# sang_bu.net
KiCad netlist of a schematic drawn in EAGLE
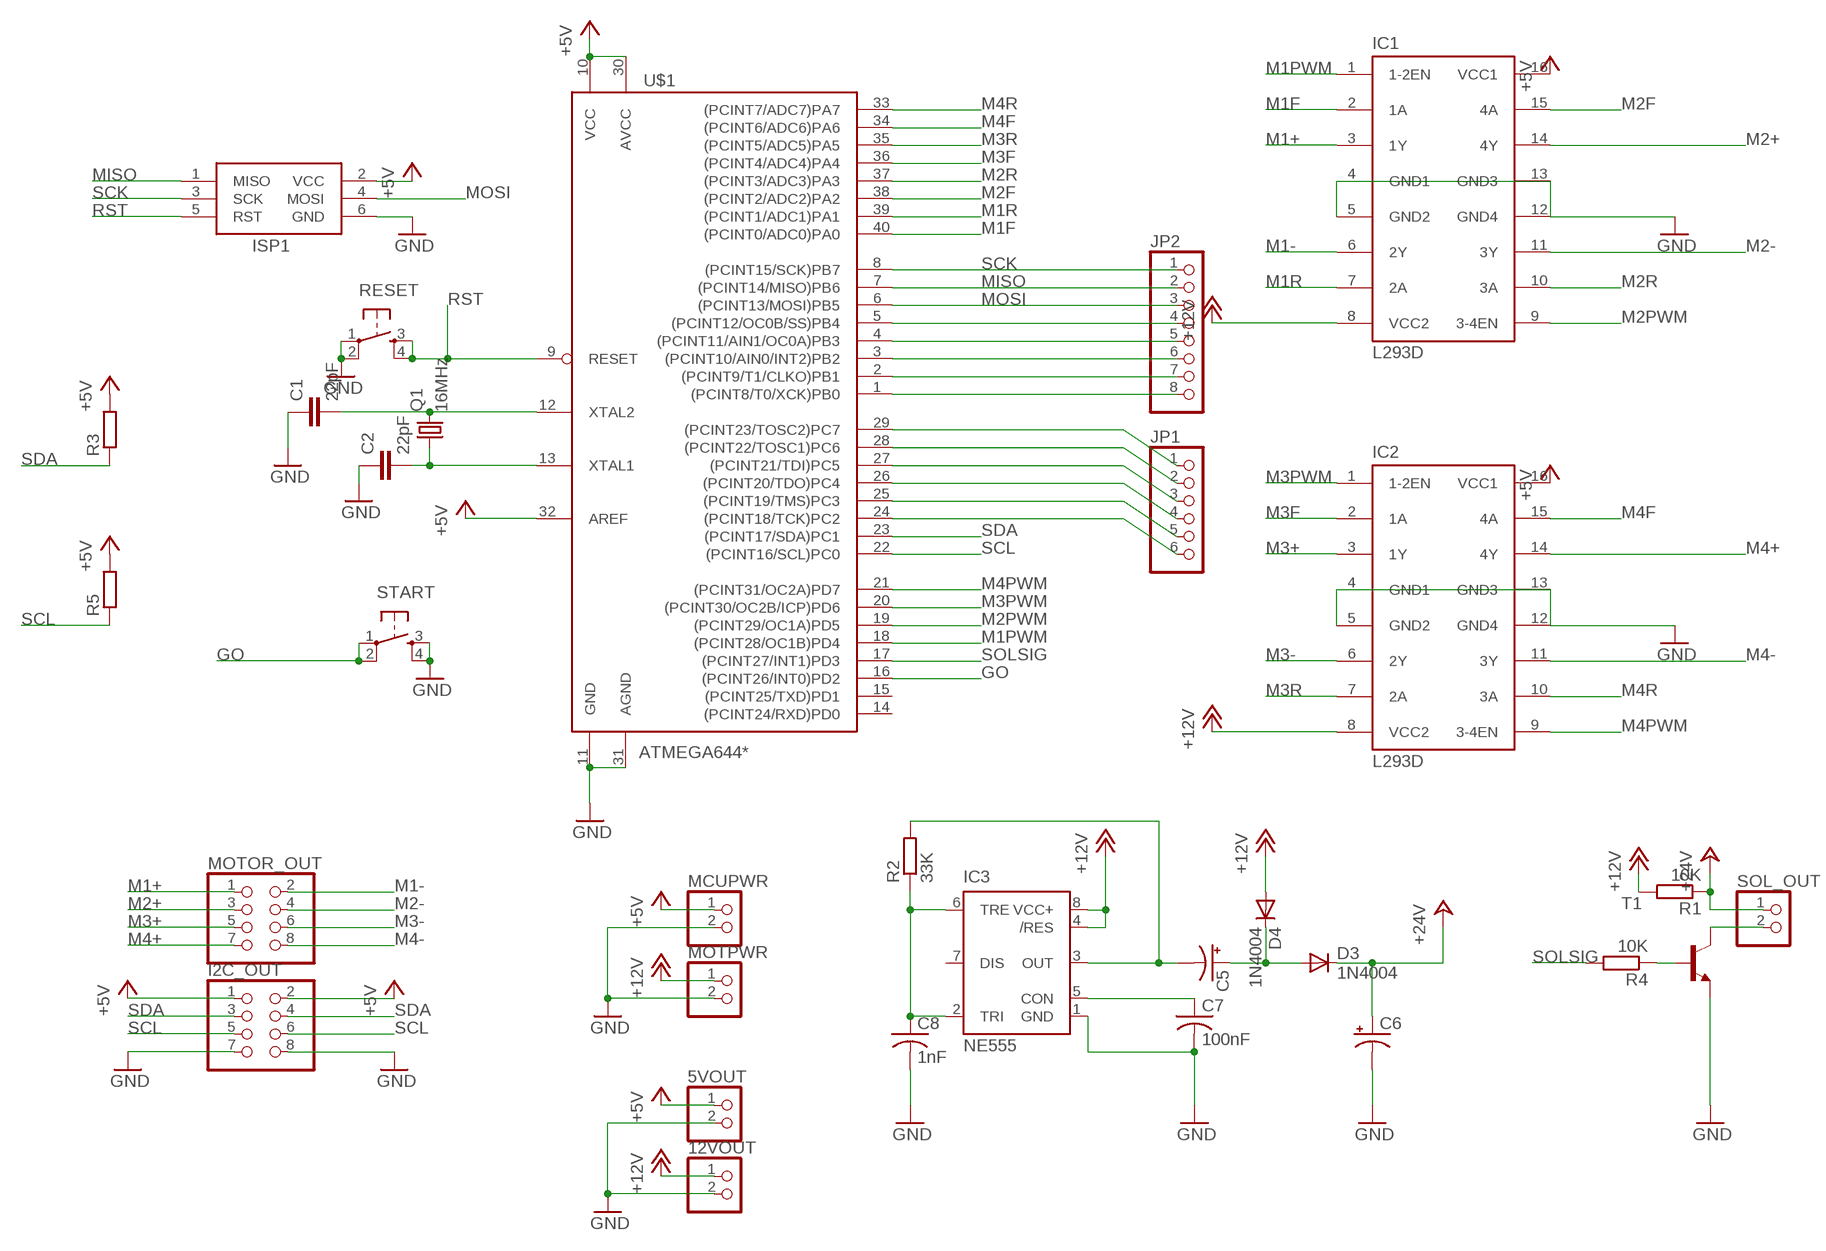
[diagram p0: schematic, sheet 1]

(export (version "E")
  (design (tool "Eeschema 10.0.6"))
  (components
    (comp (ref "5VOUT")
      (value "PINHD-1X2")
      (footprint "eagle-import:1X02")
      (libsource (lib "eagle-import") (part "PINHD-1X2"))
    )
    (comp (ref "12VOUT")
      (value "PINHD-1X2")
      (footprint "eagle-import:1X02")
      (libsource (lib "eagle-import") (part "PINHD-1X2"))
    )
    (comp (ref "C1")
      (value "22pF")
      (footprint "eagle-import:C2.5-2")
      (libsource (lib "eagle-import") (part "C2.5/2"))
    )
    (comp (ref "C2")
      (value "22pF")
      (footprint "eagle-import:C2.5-2")
      (libsource (lib "eagle-import") (part "C2.5/2"))
    )
    (comp (ref "C5")
      (value "CPOL-USE7.5-18")
      (footprint "eagle-import:E7,5-18")
      (libsource (lib "eagle-import") (part "CPOL-USE7.5-18"))
    )
    (comp (ref "C6")
      (value "CPOL-USE7.5-18")
      (footprint "eagle-import:E7,5-18")
      (libsource (lib "eagle-import") (part "CPOL-USE7.5-18"))
    )
    (comp (ref "C7")
      (value "100nF")
      (footprint "eagle-import:C025-030X050")
      (libsource (lib "eagle-import") (part "C-US025-030X050"))
    )
    (comp (ref "C8")
      (value "1nF")
      (footprint "eagle-import:C025-030X050")
      (libsource (lib "eagle-import") (part "C-US025-030X050"))
    )
    (comp (ref "D3")
      (value "1N4004")
      (footprint "eagle-import:DO41-10")
      (libsource (lib "eagle-import") (part "1N4004"))
    )
    (comp (ref "D4")
      (value "1N4004")
      (footprint "eagle-import:DO41-10")
      (libsource (lib "eagle-import") (part "1N4004"))
    )
    (comp (ref "I2C_OUT")
      (value "PINHD-2X4")
      (footprint "eagle-import:2X04")
      (libsource (lib "eagle-import") (part "PINHD-2X4"))
    )
    (comp (ref "IC1")
      (value "L293D")
      (footprint "eagle-import:DIL16")
      (libsource (lib "eagle-import") (part "L293D"))
    )
    (comp (ref "IC2")
      (value "L293D")
      (footprint "eagle-import:DIL16")
      (libsource (lib "eagle-import") (part "L293D"))
    )
    (comp (ref "IC3")
      (value "NE555")
      (footprint "eagle-import:DIL-08")
      (fields (field (name "MF") "Arrow Electronics") (field (name "MPN") "NE555N"))
      (libsource (lib "eagle-import") (part "NE555"))
    )
    (comp (ref "ISP1")
      (value "AVRISP-6")
      (footprint "eagle-import:AVRISP")
      (libsource (lib "eagle-import") (part "AVRISP-6"))
    )
    (comp (ref "JP1")
      (value "PINHD-1X6")
      (footprint "eagle-import:1X06")
      (libsource (lib "eagle-import") (part "PINHD-1X6"))
    )
    (comp (ref "JP2")
      (value "PINHD-1X8BIG")
      (footprint "eagle-import:1X08-BIG")
      (libsource (lib "eagle-import") (part "PINHD-1X8BIG"))
    )
    (comp (ref "MCUPWR")
      (value "PINHD-1X2")
      (footprint "eagle-import:1X02")
      (libsource (lib "eagle-import") (part "PINHD-1X2"))
    )
    (comp (ref "MOTOR_OUT")
      (value "PINHD-2X4")
      (footprint "eagle-import:2X04")
      (libsource (lib "eagle-import") (part "PINHD-2X4"))
    )
    (comp (ref "MOTPWR")
      (value "PINHD-1X2")
      (footprint "eagle-import:1X02")
      (libsource (lib "eagle-import") (part "PINHD-1X2"))
    )
    (comp (ref "Q1")
      (value "16MHz")
      (footprint "eagle-import:HC49U70")
      (libsource (lib "eagle-import") (part "CRYSTALHC49U70"))
    )
    (comp (ref "R1")
      (value "10K")
      (footprint "eagle-import:0207_10")
      (libsource (lib "eagle-import") (part "resistor_R-EU_0207/10"))
    )
    (comp (ref "R2")
      (value "33K")
      (footprint "eagle-import:0207_10")
      (libsource (lib "eagle-import") (part "R-EU_0207/10"))
    )
    (comp (ref "R3")
      (value "R-EU_0204/7")
      (footprint "eagle-import:0204_7")
      (libsource (lib "eagle-import") (part "resistor_R-EU_0204/7"))
    )
    (comp (ref "R4")
      (value "10K")
      (footprint "eagle-import:0207_10")
      (libsource (lib "eagle-import") (part "resistor_R-EU_0207/10"))
    )
    (comp (ref "R5")
      (value "R-EU_0204/7")
      (footprint "eagle-import:0204_7")
      (libsource (lib "eagle-import") (part "resistor_R-EU_0204/7"))
    )
    (comp (ref "RESET")
      (value "TAC_SWITCHPTH")
      (footprint "eagle-import:TACTILE-PTH")
      (libsource (lib "eagle-import") (part "TAC_SWITCHPTH"))
    )
    (comp (ref "SOL_OUT")
      (value "PINHD-1X2")
      (footprint "eagle-import:1X02")
      (libsource (lib "eagle-import") (part "PINHD-1X2"))
    )
    (comp (ref "START")
      (value "TAC_SWITCHPTH")
      (footprint "eagle-import:TACTILE-PTH")
      (libsource (lib "eagle-import") (part "TAC_SWITCHPTH"))
    )
    (comp (ref "T1")
      (value "2N2218-NPN-TO39-EBC")
      (footprint "eagle-import:TO39")
      (libsource (lib "eagle-import") (part "-NPN-TO39-EBC2N2218"))
    )
    (comp (ref "U$1")
      (value "ATMEGA644*")
      (footprint "eagle-import:ATMEGA644")
      (libsource (lib "eagle-import") (part "ATMEGA644"))
    )
  )
  (nets
    (net (code "1") (name "+5V") (class "Default")
      (node (ref "5VOUT") (pin "1") (pinfunction "1_1") (pintype "passive"))
      (node (ref "I2C_OUT") (pin "1") (pinfunction "1_1") (pintype "passive"))
      (node (ref "I2C_OUT") (pin "2") (pinfunction "2_2") (pintype "passive"))
      (node (ref "IC1") (pin "16") (pinfunction "VCC1_16") (pintype "power_in"))
      (node (ref "IC2") (pin "16") (pinfunction "VCC1_16") (pintype "power_in"))
      (node (ref "ISP1") (pin "2") (pinfunction "VCC_2") (pintype "power_in"))
      (node (ref "MCUPWR") (pin "1") (pinfunction "1_1") (pintype "passive"))
      (node (ref "R3") (pin "2") (pinfunction "2_2") (pintype "passive"))
      (node (ref "R5") (pin "2") (pinfunction "2_2") (pintype "passive"))
      (node (ref "U$1") (pin "10") (pinfunction "VCC_10") (pintype "power_in"))
      (node (ref "U$1") (pin "30") (pinfunction "AVCC_30") (pintype "power_in"))
      (node (ref "U$1") (pin "32") (pinfunction "AREF_32") (pintype "power_in"))
    )
    (net (code "2") (name "+12V") (class "Default")
      (node (ref "12VOUT") (pin "1") (pinfunction "1_1") (pintype "passive"))
      (node (ref "D4") (pin "A") (pinfunction "A_A") (pintype "passive"))
      (node (ref "IC1") (pin "8") (pinfunction "VCC2_8") (pintype "power_in"))
      (node (ref "IC2") (pin "8") (pinfunction "VCC2_8") (pintype "power_in"))
      (node (ref "IC3") (pin "4") (pinfunction "/RES_4") (pintype "input"))
      (node (ref "IC3") (pin "8") (pinfunction "VCC+_8") (pintype "power_in"))
      (node (ref "MOTPWR") (pin "1") (pinfunction "1_1") (pintype "passive"))
      (node (ref "R1") (pin "2") (pinfunction "2_2") (pintype "passive"))
    )
    (net (code "3") (name "+24V") (class "Default")
      (node (ref "C6") (pin "+") (pinfunction "+_+") (pintype "passive"))
      (node (ref "D3") (pin "C") (pinfunction "C_C") (pintype "passive"))
      (node (ref "R1") (pin "1") (pinfunction "1_1") (pintype "passive"))
      (node (ref "SOL_OUT") (pin "1") (pinfunction "1_1") (pintype "passive"))
    )
    (net (code "4") (name "/GO") (class "Default")
      (node (ref "START") (pin "1") (pinfunction "1_1") (pintype "passive"))
      (node (ref "START") (pin "2") (pinfunction "2_2") (pintype "passive"))
      (node (ref "U$1") (pin "16") (pinfunction "(PCINT26/INT0)PD2_16") (pintype "bidirectional"))
    )
    (net (code "5") (name "/M1+") (class "Default")
      (node (ref "IC1") (pin "3") (pinfunction "1Y_3") (pintype "output"))
      (node (ref "MOTOR_OUT") (pin "1") (pinfunction "1_1") (pintype "passive"))
    )
    (net (code "6") (name "/M1-") (class "Default")
      (node (ref "IC1") (pin "6") (pinfunction "2Y_6") (pintype "output"))
      (node (ref "MOTOR_OUT") (pin "2") (pinfunction "2_2") (pintype "passive"))
    )
    (net (code "7") (name "/M1F") (class "Default")
      (node (ref "IC1") (pin "2") (pinfunction "1A_2") (pintype "input"))
      (node (ref "U$1") (pin "40") (pinfunction "(PCINT0/ADC0)PA0_40") (pintype "bidirectional"))
    )
    (net (code "8") (name "/M1PWM") (class "Default")
      (node (ref "IC1") (pin "1") (pinfunction "1-2EN_1") (pintype "input"))
      (node (ref "U$1") (pin "18") (pinfunction "(PCINT28/OC1B)PD4_18") (pintype "bidirectional"))
    )
    (net (code "9") (name "/M1R") (class "Default")
      (node (ref "IC1") (pin "7") (pinfunction "2A_7") (pintype "input"))
      (node (ref "U$1") (pin "39") (pinfunction "(PCINT1/ADC1)PA1_39") (pintype "bidirectional"))
    )
    (net (code "10") (name "/M2+") (class "Default")
      (node (ref "IC1") (pin "14") (pinfunction "4Y_14") (pintype "output"))
      (node (ref "MOTOR_OUT") (pin "3") (pinfunction "3_3") (pintype "passive"))
    )
    (net (code "11") (name "/M2-") (class "Default")
      (node (ref "IC1") (pin "11") (pinfunction "3Y_11") (pintype "output"))
      (node (ref "MOTOR_OUT") (pin "4") (pinfunction "4_4") (pintype "passive"))
    )
    (net (code "12") (name "/M2F") (class "Default")
      (node (ref "IC1") (pin "15") (pinfunction "4A_15") (pintype "input"))
      (node (ref "U$1") (pin "38") (pinfunction "(PCINT2/ADC2)PA2_38") (pintype "bidirectional"))
    )
    (net (code "13") (name "/M2PWM") (class "Default")
      (node (ref "IC1") (pin "9") (pinfunction "3-4EN_9") (pintype "input"))
      (node (ref "U$1") (pin "19") (pinfunction "(PCINT29/OC1A)PD5_19") (pintype "bidirectional"))
    )
    (net (code "14") (name "/M2R") (class "Default")
      (node (ref "IC1") (pin "10") (pinfunction "3A_10") (pintype "input"))
      (node (ref "U$1") (pin "37") (pinfunction "(PCINT3/ADC3)PA3_37") (pintype "bidirectional"))
    )
    (net (code "15") (name "/M3+") (class "Default")
      (node (ref "IC2") (pin "3") (pinfunction "1Y_3") (pintype "output"))
      (node (ref "MOTOR_OUT") (pin "5") (pinfunction "5_5") (pintype "passive"))
    )
    (net (code "16") (name "/M3-") (class "Default")
      (node (ref "IC2") (pin "6") (pinfunction "2Y_6") (pintype "output"))
      (node (ref "MOTOR_OUT") (pin "6") (pinfunction "6_6") (pintype "passive"))
    )
    (net (code "17") (name "/M3F") (class "Default")
      (node (ref "IC2") (pin "2") (pinfunction "1A_2") (pintype "input"))
      (node (ref "U$1") (pin "36") (pinfunction "(PCINT4/ADC4)PA4_36") (pintype "bidirectional"))
    )
    (net (code "18") (name "/M3PWM") (class "Default")
      (node (ref "IC2") (pin "1") (pinfunction "1-2EN_1") (pintype "input"))
      (node (ref "U$1") (pin "20") (pinfunction "(PCINT30/OC2B/ICP)PD6_20") (pintype "bidirectional"))
    )
    (net (code "19") (name "/M3R") (class "Default")
      (node (ref "IC2") (pin "7") (pinfunction "2A_7") (pintype "input"))
      (node (ref "U$1") (pin "35") (pinfunction "(PCINT5/ADC5)PA5_35") (pintype "bidirectional"))
    )
    (net (code "20") (name "/M4+") (class "Default")
      (node (ref "IC2") (pin "14") (pinfunction "4Y_14") (pintype "output"))
      (node (ref "MOTOR_OUT") (pin "7") (pinfunction "7_7") (pintype "passive"))
    )
    (net (code "21") (name "/M4-") (class "Default")
      (node (ref "IC2") (pin "11") (pinfunction "3Y_11") (pintype "output"))
      (node (ref "MOTOR_OUT") (pin "8") (pinfunction "8_8") (pintype "passive"))
    )
    (net (code "22") (name "/M4F") (class "Default")
      (node (ref "IC2") (pin "15") (pinfunction "4A_15") (pintype "input"))
      (node (ref "U$1") (pin "34") (pinfunction "(PCINT6/ADC6)PA6_34") (pintype "bidirectional"))
    )
    (net (code "23") (name "/M4PWM") (class "Default")
      (node (ref "IC2") (pin "9") (pinfunction "3-4EN_9") (pintype "input"))
      (node (ref "U$1") (pin "21") (pinfunction "(PCINT31/OC2A)PD7_21") (pintype "bidirectional"))
    )
    (net (code "24") (name "/M4R") (class "Default")
      (node (ref "IC2") (pin "10") (pinfunction "3A_10") (pintype "input"))
      (node (ref "U$1") (pin "33") (pinfunction "(PCINT7/ADC7)PA7_33") (pintype "bidirectional"))
    )
    (net (code "25") (name "/MISO") (class "Default")
      (node (ref "ISP1") (pin "1") (pinfunction "MISO_1") (pintype "input"))
      (node (ref "JP2") (pin "2") (pinfunction "2_2") (pintype "passive"))
      (node (ref "U$1") (pin "7") (pinfunction "(PCINT14/MISO)PB6_7") (pintype "bidirectional"))
    )
    (net (code "26") (name "/MOSI") (class "Default")
      (node (ref "ISP1") (pin "4") (pinfunction "MOSI_4") (pintype "output"))
      (node (ref "JP2") (pin "3") (pinfunction "3_3") (pintype "passive"))
      (node (ref "U$1") (pin "6") (pinfunction "(PCINT13/MOSI)PB5_6") (pintype "bidirectional"))
    )
    (net (code "27") (name "/RST") (class "Default")
      (node (ref "ISP1") (pin "5") (pinfunction "RST_5") (pintype "output"))
      (node (ref "RESET") (pin "3") (pinfunction "3_3") (pintype "passive"))
      (node (ref "RESET") (pin "4") (pinfunction "4_4") (pintype "passive"))
      (node (ref "U$1") (pin "9") (pinfunction "RESET_9") (pintype "input"))
    )
    (net (code "28") (name "/SCK") (class "Default")
      (node (ref "ISP1") (pin "3") (pinfunction "SCK_3") (pintype "output"))
      (node (ref "JP2") (pin "1") (pinfunction "1_1") (pintype "passive"))
      (node (ref "U$1") (pin "8") (pinfunction "(PCINT15/SCK)PB7_8") (pintype "bidirectional"))
    )
    (net (code "29") (name "/SCL") (class "Default")
      (node (ref "I2C_OUT") (pin "5") (pinfunction "5_5") (pintype "passive"))
      (node (ref "I2C_OUT") (pin "6") (pinfunction "6_6") (pintype "passive"))
      (node (ref "R5") (pin "1") (pinfunction "1_1") (pintype "passive"))
      (node (ref "U$1") (pin "22") (pinfunction "(PCINT16/SCL)PC0_22") (pintype "bidirectional"))
    )
    (net (code "30") (name "/SDA") (class "Default")
      (node (ref "I2C_OUT") (pin "3") (pinfunction "3_3") (pintype "passive"))
      (node (ref "I2C_OUT") (pin "4") (pinfunction "4_4") (pintype "passive"))
      (node (ref "R3") (pin "1") (pinfunction "1_1") (pintype "passive"))
      (node (ref "U$1") (pin "23") (pinfunction "(PCINT17/SDA)PC1_23") (pintype "bidirectional"))
    )
    (net (code "31") (name "/SOLSIG") (class "Default")
      (node (ref "R4") (pin "2") (pinfunction "2_2") (pintype "passive"))
      (node (ref "U$1") (pin "17") (pinfunction "(PCINT27/INT1)PD3_17") (pintype "bidirectional"))
    )
    (net (code "32") (name "GND") (class "Default")
      (node (ref "12VOUT") (pin "2") (pinfunction "2_2") (pintype "passive"))
      (node (ref "5VOUT") (pin "2") (pinfunction "2_2") (pintype "passive"))
      (node (ref "C1") (pin "1") (pinfunction "1_1") (pintype "passive"))
      (node (ref "C2") (pin "1") (pinfunction "1_1") (pintype "passive"))
      (node (ref "C6") (pin "-") (pinfunction "-_-") (pintype "passive"))
      (node (ref "C7") (pin "2") (pinfunction "2_2") (pintype "passive"))
      (node (ref "C8") (pin "2") (pinfunction "2_2") (pintype "passive"))
      (node (ref "I2C_OUT") (pin "7") (pinfunction "7_7") (pintype "passive"))
      (node (ref "I2C_OUT") (pin "8") (pinfunction "8_8") (pintype "passive"))
      (node (ref "IC1") (pin "12") (pinfunction "GND4_12") (pintype "power_in"))
      (node (ref "IC1") (pin "13") (pinfunction "GND3_13") (pintype "power_in"))
      (node (ref "IC1") (pin "4") (pinfunction "GND1_4") (pintype "power_in"))
      (node (ref "IC1") (pin "5") (pinfunction "GND2_5") (pintype "power_in"))
      (node (ref "IC2") (pin "12") (pinfunction "GND4_12") (pintype "power_in"))
      (node (ref "IC2") (pin "13") (pinfunction "GND3_13") (pintype "power_in"))
      (node (ref "IC2") (pin "4") (pinfunction "GND1_4") (pintype "power_in"))
      (node (ref "IC2") (pin "5") (pinfunction "GND2_5") (pintype "power_in"))
      (node (ref "IC3") (pin "1") (pinfunction "GND_1") (pintype "power_in"))
      (node (ref "ISP1") (pin "6") (pinfunction "GND_6") (pintype "power_in"))
      (node (ref "MCUPWR") (pin "2") (pinfunction "2_2") (pintype "passive"))
      (node (ref "MOTPWR") (pin "2") (pinfunction "2_2") (pintype "passive"))
      (node (ref "RESET") (pin "1") (pinfunction "1_1") (pintype "passive"))
      (node (ref "RESET") (pin "2") (pinfunction "2_2") (pintype "passive"))
      (node (ref "START") (pin "3") (pinfunction "3_3") (pintype "passive"))
      (node (ref "START") (pin "4") (pinfunction "4_4") (pintype "passive"))
      (node (ref "T1") (pin "1") (pinfunction "E_1") (pintype "passive"))
      (node (ref "U$1") (pin "11") (pinfunction "GND_11") (pintype "power_in"))
      (node (ref "U$1") (pin "31") (pinfunction "AGND_31") (pintype "power_in"))
    )
    (net (code "33") (name "Net-(C5-Pad+)") (class "Default")
      (node (ref "C5") (pin "+") (pinfunction "+_+") (pintype "passive"))
      (node (ref "D3") (pin "A") (pinfunction "A_A") (pintype "passive"))
      (node (ref "D4") (pin "C") (pinfunction "C_C") (pintype "passive"))
    )
    (net (code "34") (name "Net-(IC3-CON)") (class "Default")
      (node (ref "C7") (pin "1") (pinfunction "1_1") (pintype "passive"))
      (node (ref "IC3") (pin "5") (pinfunction "CON_5") (pintype "input"))
    )
    (net (code "35") (name "Net-(IC3-OUT)") (class "Default")
      (node (ref "C5") (pin "-") (pinfunction "-_-") (pintype "passive"))
      (node (ref "IC3") (pin "3") (pinfunction "OUT_3") (pintype "output"))
      (node (ref "R2") (pin "2") (pinfunction "2_2") (pintype "passive"))
    )
    (net (code "36") (name "Net-(IC3-TRE)") (class "Default")
      (node (ref "C8") (pin "1") (pinfunction "1_1") (pintype "passive"))
      (node (ref "IC3") (pin "2") (pinfunction "TRI_2") (pintype "input"))
      (node (ref "IC3") (pin "6") (pinfunction "TRE_6") (pintype "input"))
      (node (ref "R2") (pin "1") (pinfunction "1_1") (pintype "passive"))
    )
    (net (code "37") (name "Net-(T1-B)") (class "Default")
      (node (ref "R4") (pin "1") (pinfunction "1_1") (pintype "passive"))
      (node (ref "T1") (pin "2") (pinfunction "B_2") (pintype "passive"))
    )
    (net (code "38") (name "Net-(T1-C)") (class "Default")
      (node (ref "SOL_OUT") (pin "2") (pinfunction "2_2") (pintype "passive"))
      (node (ref "T1") (pin "3") (pinfunction "C_3") (pintype "passive"))
    )
    (net (code "39") (name "Net-(U$1-(PCINT8{slash}T0{slash}XCK)PB0)") (class "Default")
      (node (ref "JP2") (pin "8") (pinfunction "8_8") (pintype "passive"))
      (node (ref "U$1") (pin "1") (pinfunction "(PCINT8/T0/XCK)PB0_1") (pintype "bidirectional"))
    )
    (net (code "40") (name "Net-(U$1-(PCINT9{slash}T1{slash}CLKO)PB1)") (class "Default")
      (node (ref "JP2") (pin "7") (pinfunction "7_7") (pintype "passive"))
      (node (ref "U$1") (pin "2") (pinfunction "(PCINT9/T1/CLKO)PB1_2") (pintype "bidirectional"))
    )
    (net (code "41") (name "Net-(U$1-(PCINT10{slash}AIN0{slash}INT2)PB2)") (class "Default")
      (node (ref "JP2") (pin "6") (pinfunction "6_6") (pintype "passive"))
      (node (ref "U$1") (pin "3") (pinfunction "(PCINT10/AIN0/INT2)PB2_3") (pintype "bidirectional"))
    )
    (net (code "42") (name "Net-(U$1-(PCINT11{slash}AIN1{slash}OC0A)PB3)") (class "Default")
      (node (ref "JP2") (pin "5") (pinfunction "5_5") (pintype "passive"))
      (node (ref "U$1") (pin "4") (pinfunction "(PCINT11/AIN1/OC0A)PB3_4") (pintype "bidirectional"))
    )
    (net (code "43") (name "Net-(U$1-(PCINT12{slash}OC0B{slash}SS)PB4)") (class "Default")
      (node (ref "JP2") (pin "4") (pinfunction "4_4") (pintype "passive"))
      (node (ref "U$1") (pin "5") (pinfunction "(PCINT12/OC0B/SS)PB4_5") (pintype "bidirectional"))
    )
    (net (code "44") (name "Net-(U$1-(PCINT18{slash}TCK)PC2)") (class "Default")
      (node (ref "JP1") (pin "6") (pinfunction "6_6") (pintype "passive"))
      (node (ref "U$1") (pin "24") (pinfunction "(PCINT18/TCK)PC2_24") (pintype "bidirectional"))
    )
    (net (code "45") (name "Net-(U$1-(PCINT19{slash}TMS)PC3)") (class "Default")
      (node (ref "JP1") (pin "5") (pinfunction "5_5") (pintype "passive"))
      (node (ref "U$1") (pin "25") (pinfunction "(PCINT19/TMS)PC3_25") (pintype "bidirectional"))
    )
    (net (code "46") (name "Net-(U$1-(PCINT20{slash}TDO)PC4)") (class "Default")
      (node (ref "JP1") (pin "4") (pinfunction "4_4") (pintype "passive"))
      (node (ref "U$1") (pin "26") (pinfunction "(PCINT20/TDO)PC4_26") (pintype "bidirectional"))
    )
    (net (code "47") (name "Net-(U$1-(PCINT21{slash}TDI)PC5)") (class "Default")
      (node (ref "JP1") (pin "3") (pinfunction "3_3") (pintype "passive"))
      (node (ref "U$1") (pin "27") (pinfunction "(PCINT21/TDI)PC5_27") (pintype "bidirectional"))
    )
    (net (code "48") (name "Net-(U$1-(PCINT22{slash}TOSC1)PC6)") (class "Default")
      (node (ref "JP1") (pin "2") (pinfunction "2_2") (pintype "passive"))
      (node (ref "U$1") (pin "28") (pinfunction "(PCINT22/TOSC1)PC6_28") (pintype "bidirectional"))
    )
    (net (code "49") (name "Net-(U$1-(PCINT23{slash}TOSC2)PC7)") (class "Default")
      (node (ref "JP1") (pin "1") (pinfunction "1_1") (pintype "passive"))
      (node (ref "U$1") (pin "29") (pinfunction "(PCINT23/TOSC2)PC7_29") (pintype "bidirectional"))
    )
    (net (code "50") (name "Net-(U$1-XTAL1)") (class "Default")
      (node (ref "C2") (pin "2") (pinfunction "2_2") (pintype "passive"))
      (node (ref "Q1") (pin "1") (pinfunction "1_1") (pintype "passive"))
      (node (ref "U$1") (pin "13") (pinfunction "XTAL1_13") (pintype "bidirectional"))
    )
    (net (code "51") (name "Net-(U$1-XTAL2)") (class "Default")
      (node (ref "C1") (pin "2") (pinfunction "2_2") (pintype "passive"))
      (node (ref "Q1") (pin "2") (pinfunction "2_2") (pintype "passive"))
      (node (ref "U$1") (pin "12") (pinfunction "XTAL2_12") (pintype "bidirectional"))
    )
    (net (code "52") (name "unconnected-(IC3-DIS-Pad7)") (class "Default")
      (node (ref "IC3") (pin "7") (pinfunction "DIS_7") (pintype "input"))
    )
    (net (code "53") (name "unconnected-(U$1-(PCINT24{slash}RXD)PD0-Pad14)") (class "Default")
      (node (ref "U$1") (pin "14") (pinfunction "(PCINT24/RXD)PD0_14") (pintype "bidirectional"))
    )
    (net (code "54") (name "unconnected-(U$1-(PCINT25{slash}TXD)PD1-Pad15)") (class "Default")
      (node (ref "U$1") (pin "15") (pinfunction "(PCINT25/TXD)PD1_15") (pintype "bidirectional"))
    )
  )
)
